# PA.net
KiCad netlist of a schematic drawn in Altium Designer
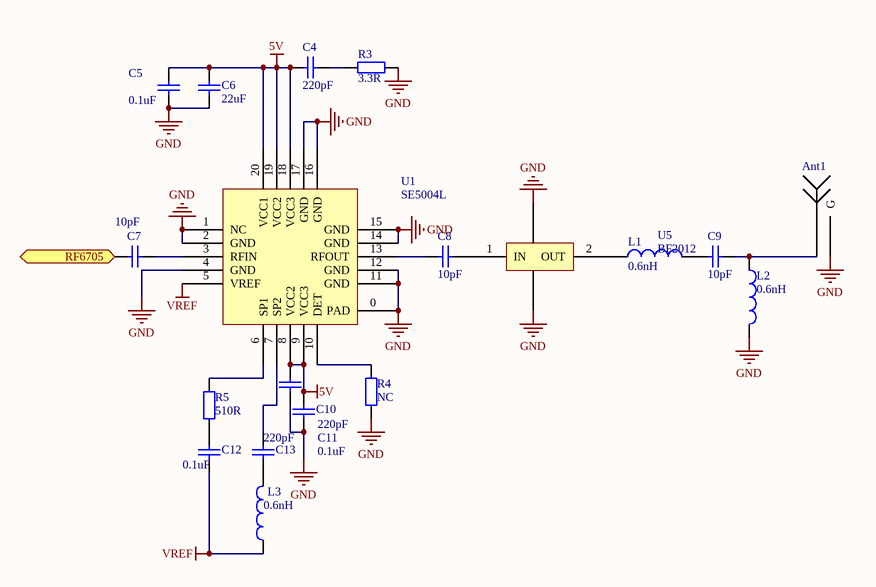
[diagram p0: PA.SchDoc]

(export (version "E")
  (design (tool "Eeschema 10.0.6"))
  (components
    (comp (ref "Ant1") (value "Antenna") (footprint "SMA") (libsource (lib "RTC6705") (part "Antenna")))
    (comp (ref "C4")
      (value "220pF")
      (footprint "0402")
      (description "Capacitor")
      (fields (field (name "Comment") "Cap") (field (name "PUBLISHER") "Altium Limited"))
      (libsource (lib "RTC6705") (part "Cap"))
    )
    (comp (ref "C5")
      (value "0.1uF")
      (footprint "0402")
      (description "Capacitor")
      (fields (field (name "Comment") "Cap") (field (name "PUBLISHER") "Altium Limited"))
      (libsource (lib "RTC6705") (part "Cap"))
    )
    (comp (ref "C6")
      (value "22uF")
      (footprint "0402")
      (description "Capacitor")
      (fields (field (name "Comment") "Cap") (field (name "PUBLISHER") "Altium Limited"))
      (libsource (lib "RTC6705") (part "Cap"))
    )
    (comp (ref "C7")
      (value "10pF")
      (footprint "0402")
      (description "Capacitor")
      (fields (field (name "Comment") "Cap") (field (name "PUBLISHER") "Altium Limited"))
      (libsource (lib "RTC6705") (part "Cap"))
    )
    (comp (ref "C8")
      (value "10pF")
      (footprint "0402")
      (description "Capacitor")
      (fields (field (name "Comment") "Cap") (field (name "PUBLISHER") "Altium Limited"))
      (libsource (lib "RTC6705") (part "Cap"))
    )
    (comp (ref "C9")
      (value "10pF")
      (footprint "0402")
      (description "Capacitor")
      (fields (field (name "Comment") "Cap") (field (name "PUBLISHER") "Altium Limited"))
      (libsource (lib "RTC6705") (part "Cap"))
    )
    (comp (ref "C10")
      (value "0.1uF")
      (footprint "0402")
      (description "Capacitor")
      (fields (field (name "Comment") "Cap") (field (name "PUBLISHER") "Altium Limited"))
      (libsource (lib "RTC6705") (part "Cap"))
    )
    (comp (ref "C11")
      (value "220pF")
      (footprint "0402")
      (description "Capacitor")
      (fields (field (name "Comment") "Cap") (field (name "PUBLISHER") "Altium Limited"))
      (libsource (lib "RTC6705") (part "Cap"))
    )
    (comp (ref "C12")
      (value "0.1uF")
      (footprint "0402")
      (description "Capacitor")
      (fields (field (name "Comment") "Cap") (field (name "PUBLISHER") "Altium Limited"))
      (libsource (lib "RTC6705") (part "Cap"))
    )
    (comp (ref "C13")
      (value "220pF")
      (footprint "0402")
      (description "Capacitor")
      (fields (field (name "Comment") "Cap") (field (name "PUBLISHER") "Altium Limited"))
      (libsource (lib "RTC6705") (part "Cap"))
    )
    (comp (ref "L1")
      (value "0.6nH")
      (footprint "0402")
      (description "Inductor")
      (fields (field (name "PUBLISHER") "Altium Limited"))
      (libsource (lib "Miscellaneous Devices") (part "Inductor"))
    )
    (comp (ref "L2")
      (value "0.6nH")
      (footprint "0402")
      (description "Inductor")
      (fields (field (name "PUBLISHER") "Altium Limited"))
      (libsource (lib "Miscellaneous Devices") (part "Inductor"))
    )
    (comp (ref "L3")
      (value "0.6nH")
      (footprint "0402")
      (description "Inductor")
      (fields (field (name "PUBLISHER") "Altium Limited"))
      (libsource (lib "Miscellaneous Devices") (part "Inductor"))
    )
    (comp (ref "R3")
      (value "3.3R")
      (footprint "0402")
      (description "Resistor")
      (fields (field (name "Comment") "Res2") (field (name "PUBLISHER") "Altium Limited"))
      (libsource (lib "") (part "Res2_1"))
    )
    (comp (ref "R4")
      (value "NC")
      (footprint "0402")
      (description "Resistor")
      (fields (field (name "Comment") "Res2") (field (name "PUBLISHER") "Altium Limited"))
      (libsource (lib "RTC6705") (part "Res2"))
    )
    (comp (ref "R5")
      (value "510R")
      (footprint "0402")
      (description "Resistor")
      (fields (field (name "Comment") "Res2") (field (name "PUBLISHER") "Altium Limited"))
      (libsource (lib "RTC6705") (part "Res2"))
    )
    (comp (ref "U1") (value "SE5004L") (footprint "SE5004L") (libsource (lib "RTC6705") (part "SE5004L")))
    (comp (ref "U5") (value "BF2012") (footprint "BF2012") (libsource (lib "RTC6705") (part "BF2012")))
  )
  (nets
    (net (code "1") (name "/RF6705") (class "Default")
      (node (ref "C7") (pin "1") (pinfunction "1_1") (pintype "passive"))
    )
    (net (code "2") (name "5V") (class "Default")
      (node (ref "C10") (pin "2") (pinfunction "2_2") (pintype "passive"))
      (node (ref "C11") (pin "2") (pinfunction "2_2") (pintype "passive"))
      (node (ref "C4") (pin "2") (pinfunction "2_2") (pintype "passive"))
      (node (ref "C5") (pin "2") (pinfunction "2_2") (pintype "passive"))
      (node (ref "C6") (pin "2") (pinfunction "2_2") (pintype "passive"))
      (node (ref "U1") (pin "18") (pinfunction "VCC3_18") (pintype "passive"))
      (node (ref "U1") (pin "19") (pinfunction "VCC2_19") (pintype "passive"))
      (node (ref "U1") (pin "20") (pinfunction "VCC1_20") (pintype "passive"))
      (node (ref "U1") (pin "8") (pinfunction "VCC2_8") (pintype "passive"))
      (node (ref "U1") (pin "9") (pinfunction "VCC3_9") (pintype "passive"))
    )
    (net (code "3") (name "GND") (class "Default")
      (node (ref "Ant1") (pin "GND") (pinfunction "G_GND") (pintype "passive"))
      (node (ref "C10") (pin "1") (pinfunction "1_1") (pintype "passive"))
      (node (ref "C11") (pin "1") (pinfunction "1_1") (pintype "passive"))
      (node (ref "C5") (pin "1") (pinfunction "1_1") (pintype "passive"))
      (node (ref "C6") (pin "1") (pinfunction "1_1") (pintype "passive"))
      (node (ref "L2") (pin "2") (pinfunction "2_2") (pintype "passive"))
      (node (ref "R3") (pin "1") (pinfunction "1_1") (pintype "passive"))
      (node (ref "R4") (pin "1") (pinfunction "1_1") (pintype "passive"))
      (node (ref "U1") (pin "0") (pinfunction "PAD_0") (pintype "passive"))
      (node (ref "U1") (pin "1") (pinfunction "NC_1") (pintype "passive"))
      (node (ref "U1") (pin "11") (pinfunction "GND_11") (pintype "passive"))
      (node (ref "U1") (pin "12") (pinfunction "GND_12") (pintype "passive"))
      (node (ref "U1") (pin "14") (pinfunction "GND_14") (pintype "passive"))
      (node (ref "U1") (pin "15") (pinfunction "GND_15") (pintype "passive"))
      (node (ref "U1") (pin "16") (pinfunction "GND_16") (pintype "passive"))
      (node (ref "U1") (pin "17") (pinfunction "GND_17") (pintype "passive"))
      (node (ref "U1") (pin "2") (pinfunction "GND_2") (pintype "passive"))
      (node (ref "U1") (pin "4") (pinfunction "GND_4") (pintype "passive"))
      (node (ref "U5") (pin "0") (pinfunction "OUT_0") (pintype "passive"))
      (node (ref "U5") (pin "1") (pinfunction "OUT_1") (pintype "passive"))
    )
    (net (code "4") (name "Net-(Ant1-Pad1)") (class "Default")
      (node (ref "Ant1") (pin "1") (pinfunction "1_1") (pintype "passive"))
      (node (ref "C9") (pin "2") (pinfunction "2_2") (pintype "passive"))
      (node (ref "L2") (pin "1") (pinfunction "1_1") (pintype "passive"))
    )
    (net (code "5") (name "Net-(C4-Pad1)") (class "Default")
      (node (ref "C4") (pin "1") (pinfunction "1_1") (pintype "passive"))
      (node (ref "R3") (pin "2") (pinfunction "2_2") (pintype "passive"))
    )
    (net (code "6") (name "Net-(C9-Pad1)") (class "Default")
      (node (ref "C9") (pin "1") (pinfunction "1_1") (pintype "passive"))
      (node (ref "L1") (pin "2") (pinfunction "2_2") (pintype "passive"))
    )
    (net (code "7") (name "Net-(C12-Pad2)") (class "Default")
      (node (ref "C12") (pin "2") (pinfunction "2_2") (pintype "passive"))
      (node (ref "R5") (pin "1") (pinfunction "1_1") (pintype "passive"))
    )
    (net (code "8") (name "Net-(C13-Pad1)") (class "Default")
      (node (ref "C13") (pin "1") (pinfunction "1_1") (pintype "passive"))
      (node (ref "L3") (pin "2") (pinfunction "2_2") (pintype "passive"))
    )
    (net (code "9") (name "Net-(L1-Pad1)") (class "Default")
      (node (ref "L1") (pin "1") (pinfunction "1_1") (pintype "passive"))
      (node (ref "U5") (pin "2") (pinfunction "OUT_2") (pintype "passive"))
    )
    (net (code "10") (name "Net-(U1-DET)") (class "Default")
      (node (ref "R4") (pin "2") (pinfunction "2_2") (pintype "passive"))
      (node (ref "U1") (pin "10") (pinfunction "DET_10") (pintype "passive"))
    )
    (net (code "11") (name "Net-(U1-RFIN)") (class "Default")
      (node (ref "C7") (pin "2") (pinfunction "2_2") (pintype "passive"))
      (node (ref "U1") (pin "3") (pinfunction "RFIN_3") (pintype "passive"))
    )
    (net (code "12") (name "Net-(U1-RFOUT)") (class "Default")
      (node (ref "C8") (pin "1") (pinfunction "1_1") (pintype "passive"))
      (node (ref "U1") (pin "13") (pinfunction "RFOUT_13") (pintype "passive"))
    )
    (net (code "13") (name "Net-(U1-SP1)") (class "Default")
      (node (ref "R5") (pin "2") (pinfunction "2_2") (pintype "passive"))
      (node (ref "U1") (pin "6") (pinfunction "SP1_6") (pintype "passive"))
    )
    (net (code "14") (name "Net-(U1-SP2)") (class "Default")
      (node (ref "C13") (pin "2") (pinfunction "2_2") (pintype "passive"))
      (node (ref "U1") (pin "7") (pinfunction "SP2_7") (pintype "passive"))
    )
    (net (code "15") (name "Net-(U5-IN)") (class "Default")
      (node (ref "C8") (pin "2") (pinfunction "2_2") (pintype "passive"))
      (node (ref "U5") (pin "1") (pinfunction "IN_1") (pintype "passive"))
    )
    (net (code "16") (name "VREF") (class "Default")
      (node (ref "C12") (pin "1") (pinfunction "1_1") (pintype "passive"))
      (node (ref "L3") (pin "1") (pinfunction "1_1") (pintype "passive"))
      (node (ref "U1") (pin "5") (pinfunction "VREF_5") (pintype "passive"))
    )
  )
)
